# v1_5_Solar.net
KiCad netlist of a schematic drawn in Altium Designer
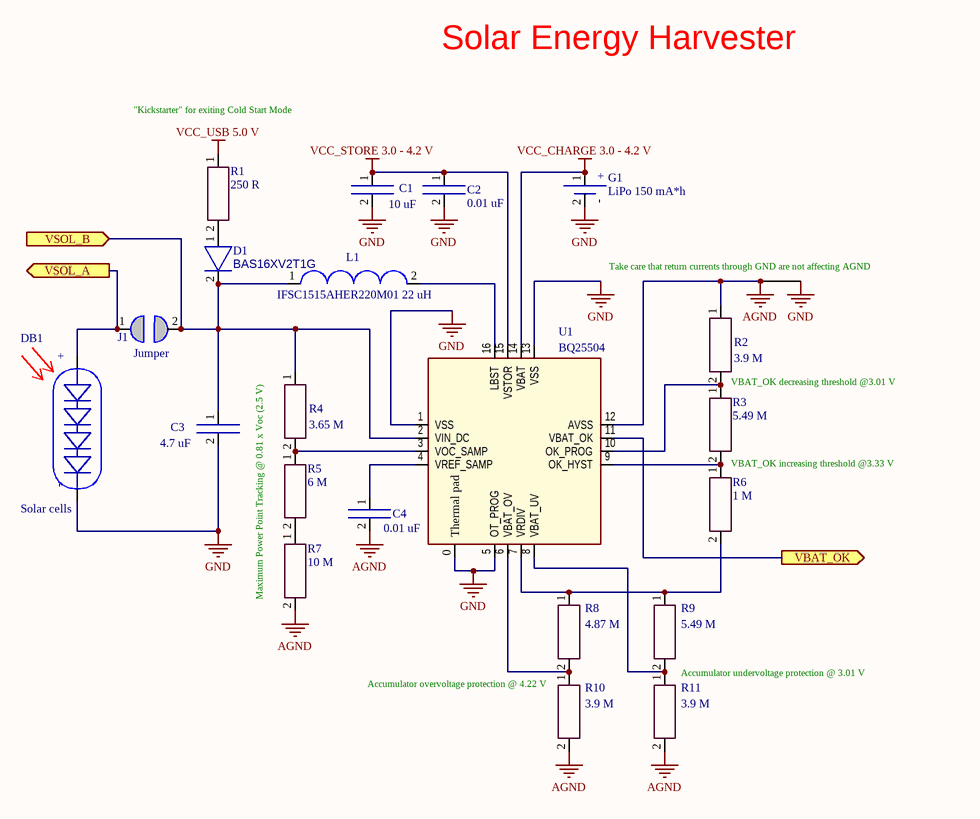
[diagram p0: v1.5 Solar.SchDoc]

(export (version "E")
  (design (tool "Eeschema 10.0.6"))
  (components
    (comp (ref "C1")
      (value "10 uF")
      (footprint "Ungravity Library:0603")
      (libsource (lib "Ungravity Library") (part "Capasistor"))
    )
    (comp (ref "C2")
      (value "0.01 uF")
      (footprint "Ungravity Library:0402")
      (libsource (lib "Ungravity Library") (part "Capasistor"))
    )
    (comp (ref "C3")
      (value "4.7 uF")
      (footprint "Ungravity Library:0402")
      (libsource (lib "Ungravity Library") (part "Capasistor"))
    )
    (comp (ref "C4")
      (value "0.01 uF")
      (footprint "Ungravity Library:0402")
      (libsource (lib "Ungravity Library") (part "Capasistor"))
    )
    (comp (ref "D1")
      (value "BAS16XV2T1G")
      (footprint "Ungravity Library:SOD-523")
      (libsource (lib "Ungravity Library") (part "Diode"))
    )
    (comp (ref "DB1")
      (value "Solar cells")
      (footprint "Ungravity Library:Solar cells")
      (libsource (lib "Ungravity Library") (part "Solar cells"))
    )
    (comp (ref "G1")
      (value "LiPo 150 mA*h")
      (footprint "Ungravity Library:LPV551230")
      (libsource (lib "Ungravity Library") (part "Accumulator"))
    )
    (comp (ref "J1")
      (value "Jumper")
      (footprint "Ungravity Library:0603 - Jumper")
      (libsource (lib "Ungravity Library") (part "Jumper"))
    )
    (comp (ref "L1")
      (value "IFSC1515AHER220M01 22 uH")
      (footprint "Ungravity Library:IFSC1515-AH-01")
      (libsource (lib "Ungravity Library") (part "Inductor"))
    )
    (comp (ref "NET TIE1")
      (value "~")
      (footprint "Ungravity Library:Net Tie")
      (libsource (lib "Ungravity Library") (part "Net Tie"))
    )
    (comp (ref "R1")
      (value "250 R")
      (footprint "Ungravity Library:0402")
      (libsource (lib "Ungravity Library") (part "Resistor"))
    )
    (comp (ref "R2")
      (value "3.9 M")
      (footprint "Ungravity Library:0402")
      (libsource (lib "Ungravity Library") (part "Resistor"))
    )
    (comp (ref "R3")
      (value "5.49 M")
      (footprint "Ungravity Library:0402")
      (libsource (lib "Ungravity Library") (part "Resistor"))
    )
    (comp (ref "R4")
      (value "3.65 M")
      (footprint "Ungravity Library:0402")
      (libsource (lib "Ungravity Library") (part "Resistor"))
    )
    (comp (ref "R5")
      (value "6 M")
      (footprint "Ungravity Library:0402")
      (libsource (lib "Ungravity Library") (part "Resistor"))
    )
    (comp (ref "R6")
      (value "1 M")
      (footprint "Ungravity Library:0402")
      (libsource (lib "Ungravity Library") (part "Resistor"))
    )
    (comp (ref "R7")
      (value "10 M")
      (footprint "Ungravity Library:0402")
      (libsource (lib "Ungravity Library") (part "Resistor"))
    )
    (comp (ref "R8")
      (value "4.87 M")
      (footprint "Ungravity Library:0402")
      (libsource (lib "Ungravity Library") (part "Resistor"))
    )
    (comp (ref "R9")
      (value "5.49 M")
      (footprint "Ungravity Library:0402")
      (libsource (lib "Ungravity Library") (part "Resistor"))
    )
    (comp (ref "R10")
      (value "3.9 M")
      (footprint "Ungravity Library:0402")
      (libsource (lib "Ungravity Library") (part "Resistor"))
    )
    (comp (ref "R11")
      (value "3.9 M")
      (footprint "Ungravity Library:0402")
      (libsource (lib "Ungravity Library") (part "Resistor"))
    )
    (comp (ref "U1")
      (value "BQ25504")
      (footprint "Ungravity Library:BQ25504")
      (libsource (lib "Ungravity Library") (part "BQ25504"))
    )
  )
  (nets
    (net (code "1") (name "/VBAT_OK") (class "Default")
      (node (ref "U1") (pin "11") (pinfunction "VBAT_OK_11") (pintype "passive"))
    )
    (net (code "2") (name "/VSOL_A") (class "Default") (node (ref "J1") (pin "1") (pintype "passive")))
    (net (code "3") (name "/VSOL_B") (class "Default")
      (node (ref "C3") (pin "1") (pinfunction "1_1") (pintype "passive"))
      (node (ref "D1") (pin "2") (pinfunction "2_2") (pintype "passive"))
      (node (ref "J1") (pin "2") (pintype "passive"))
      (node (ref "L1") (pin "1") (pinfunction "1_1") (pintype "passive"))
      (node (ref "R4") (pin "1") (pinfunction "1_1") (pintype "passive"))
      (node (ref "U1") (pin "2") (pinfunction "VIN_DC_2") (pintype "passive"))
    )
    (net (code "4") (name "AGND") (class "Default")
      (node (ref "C4") (pin "2") (pinfunction "2_2") (pintype "passive"))
      (node (ref "NET TIE1") (pin "1") (pintype "passive"))
      (node (ref "R10") (pin "2") (pinfunction "2_2") (pintype "passive"))
      (node (ref "R11") (pin "2") (pinfunction "2_2") (pintype "passive"))
      (node (ref "R2") (pin "1") (pinfunction "1_1") (pintype "passive"))
      (node (ref "R7") (pin "2") (pinfunction "2_2") (pintype "passive"))
      (node (ref "U1") (pin "12") (pinfunction "AVSS_12") (pintype "passive"))
    )
    (net (code "5") (name "GND") (class "Default")
      (node (ref "C1") (pin "2") (pinfunction "2_2") (pintype "passive"))
      (node (ref "C2") (pin "2") (pinfunction "2_2") (pintype "passive"))
      (node (ref "C3") (pin "2") (pinfunction "2_2") (pintype "passive"))
      (node (ref "G1") (pin "2") (pinfunction "2_2") (pintype "passive"))
      (node (ref "NET TIE1") (pin "2") (pintype "passive"))
      (node (ref "U1") (pin "0") (pinfunction "Thermal_pad_0") (pintype "passive"))
      (node (ref "U1") (pin "1") (pinfunction "VSS_1") (pintype "passive"))
      (node (ref "U1") (pin "13") (pinfunction "VSS_13") (pintype "passive"))
      (node (ref "U1") (pin "5") (pinfunction "OT_PROG_5") (pintype "passive"))
    )
    (net (code "6") (name "Net-(D1-Pad1)") (class "Default")
      (node (ref "D1") (pin "1") (pinfunction "1_1") (pintype "passive"))
      (node (ref "R1") (pin "2") (pinfunction "2_2") (pintype "passive"))
    )
    (net (code "7") (name "Net-(R5-Pad2)") (class "Default")
      (node (ref "R5") (pin "2") (pinfunction "2_2") (pintype "passive"))
      (node (ref "R7") (pin "1") (pinfunction "1_1") (pintype "passive"))
    )
    (net (code "8") (name "Net-(U1-LBST)") (class "Default")
      (node (ref "L1") (pin "2") (pinfunction "2_2") (pintype "passive"))
      (node (ref "U1") (pin "16") (pinfunction "LBST_16") (pintype "passive"))
    )
    (net (code "9") (name "Net-(U1-OK_HYST)") (class "Default")
      (node (ref "R3") (pin "2") (pinfunction "2_2") (pintype "passive"))
      (node (ref "R6") (pin "1") (pinfunction "1_1") (pintype "passive"))
      (node (ref "U1") (pin "9") (pinfunction "OK_HYST_9") (pintype "passive"))
    )
    (net (code "10") (name "Net-(U1-OK_PROG)") (class "Default")
      (node (ref "R2") (pin "2") (pinfunction "2_2") (pintype "passive"))
      (node (ref "R3") (pin "1") (pinfunction "1_1") (pintype "passive"))
      (node (ref "U1") (pin "10") (pinfunction "OK_PROG_10") (pintype "passive"))
    )
    (net (code "11") (name "Net-(U1-VBAT_OV)") (class "Default")
      (node (ref "R10") (pin "1") (pinfunction "1_1") (pintype "passive"))
      (node (ref "R8") (pin "2") (pinfunction "2_2") (pintype "passive"))
      (node (ref "U1") (pin "6") (pinfunction "VBAT_OV_6") (pintype "passive"))
    )
    (net (code "12") (name "Net-(U1-VBAT_UV)") (class "Default")
      (node (ref "R11") (pin "1") (pinfunction "1_1") (pintype "passive"))
      (node (ref "R9") (pin "2") (pinfunction "2_2") (pintype "passive"))
      (node (ref "U1") (pin "8") (pinfunction "VBAT_UV_8") (pintype "passive"))
    )
    (net (code "13") (name "Net-(U1-VOC_SAMP)") (class "Default")
      (node (ref "R4") (pin "2") (pinfunction "2_2") (pintype "passive"))
      (node (ref "R5") (pin "1") (pinfunction "1_1") (pintype "passive"))
      (node (ref "U1") (pin "3") (pinfunction "VOC_SAMP_3") (pintype "passive"))
    )
    (net (code "14") (name "Net-(U1-VRDIV)") (class "Default")
      (node (ref "R6") (pin "2") (pinfunction "2_2") (pintype "passive"))
      (node (ref "R8") (pin "1") (pinfunction "1_1") (pintype "passive"))
      (node (ref "R9") (pin "1") (pinfunction "1_1") (pintype "passive"))
      (node (ref "U1") (pin "7") (pinfunction "VRDIV_7") (pintype "passive"))
    )
    (net (code "15") (name "Net-(U1-VREF_SAMP)") (class "Default")
      (node (ref "C4") (pin "1") (pinfunction "1_1") (pintype "passive"))
      (node (ref "U1") (pin "4") (pinfunction "VREF_SAMP_4") (pintype "passive"))
    )
    (net (code "16") (name "VCC_CHARGE 3.0 - 4.2 V") (class "Default")
      (node (ref "G1") (pin "1") (pinfunction "1_1") (pintype "passive"))
      (node (ref "U1") (pin "14") (pinfunction "VBAT_14") (pintype "passive"))
    )
    (net (code "17") (name "VCC_STORE 3.0 - 4.2 V") (class "Default")
      (node (ref "C1") (pin "1") (pinfunction "1_1") (pintype "passive"))
      (node (ref "C2") (pin "1") (pinfunction "1_1") (pintype "passive"))
      (node (ref "U1") (pin "15") (pinfunction "VSTOR_15") (pintype "passive"))
    )
    (net (code "18") (name "VCC_USB 5.0 V") (class "Default")
      (node (ref "R1") (pin "1") (pinfunction "1_1") (pintype "passive"))
    )
  )
)
